# STM32BoardBeta2.net
KiCad netlist of a schematic drawn in EAGLE
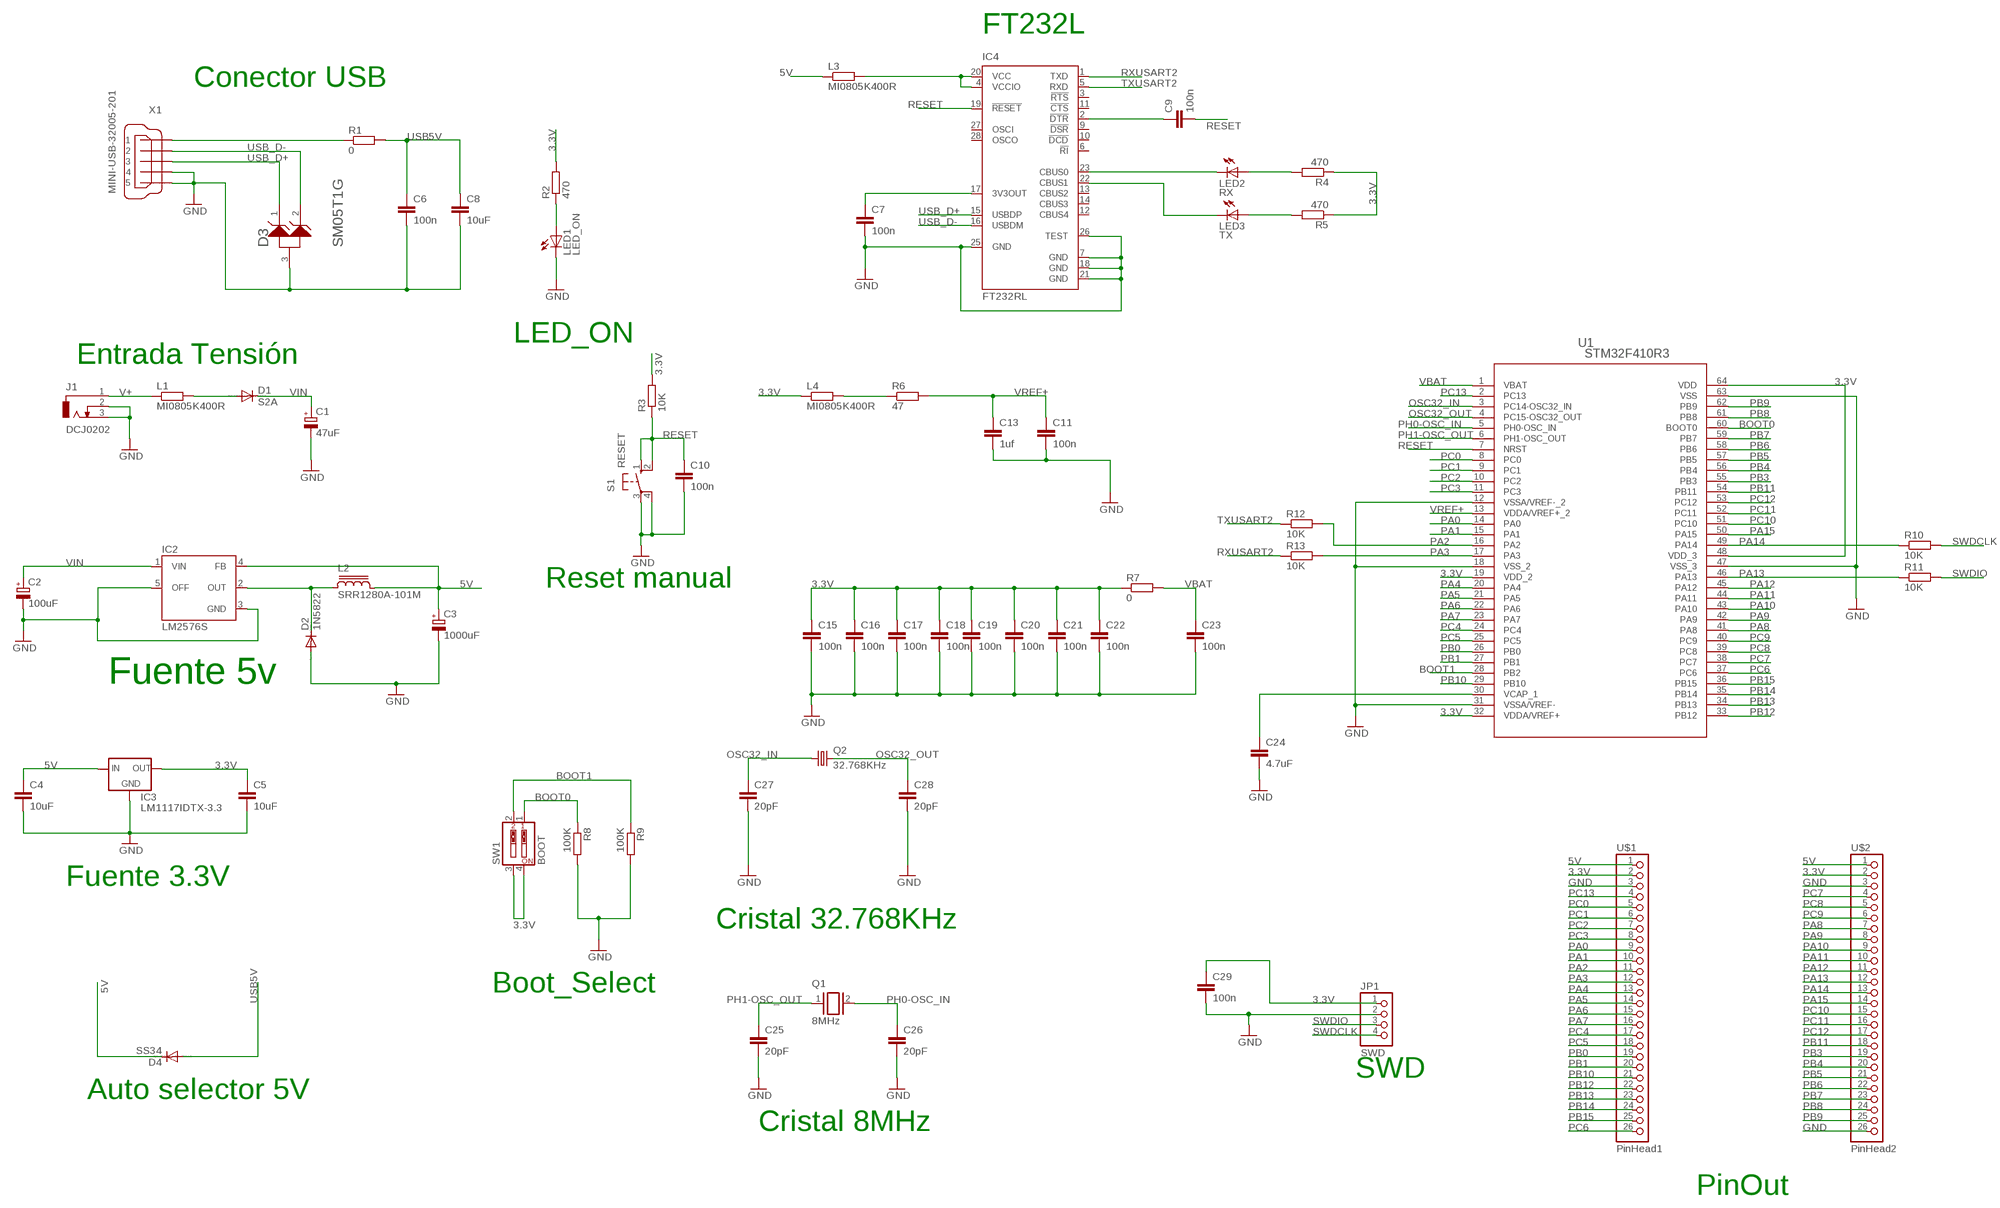
[diagram p0: schematic, sheet 1]

(export (version "E")
  (design (tool "Eeschema 10.0.6"))
  (components
    (comp (ref "C1")
      (value "47uF")
      (footprint "eagle-import:153CLV-0605")
      (libsource (lib "eagle-import") (part "CPOL-EU153CLV-0605"))
    )
    (comp (ref "C2")
      (value "100uF")
      (footprint "eagle-import:153CLV-0605")
      (libsource (lib "eagle-import") (part "CPOL-EU153CLV-0605"))
    )
    (comp (ref "C3")
      (value "1000uF")
      (footprint "eagle-import:E7,5-18")
      (libsource (lib "eagle-import") (part "CPOL-EUE7.5-18"))
    )
    (comp (ref "C4")
      (value "10uF")
      (footprint "eagle-import:C1206K")
      (libsource (lib "eagle-import") (part "C-EUC1206K"))
    )
    (comp (ref "C5")
      (value "10uF")
      (footprint "eagle-import:C1206K")
      (libsource (lib "eagle-import") (part "C-EUC1206K"))
    )
    (comp (ref "C6")
      (value "100n")
      (footprint "eagle-import:C0805K")
      (libsource (lib "eagle-import") (part "C-EUC0805K"))
    )
    (comp (ref "C7")
      (value "100n")
      (footprint "eagle-import:C0805K")
      (libsource (lib "eagle-import") (part "C-EUC0805K"))
    )
    (comp (ref "C8")
      (value "10uF")
      (footprint "eagle-import:C1206K")
      (libsource (lib "eagle-import") (part "C-EUC1206K"))
    )
    (comp (ref "C9")
      (value "100n")
      (footprint "eagle-import:C0805K")
      (libsource (lib "eagle-import") (part "C-EUC0805K"))
    )
    (comp (ref "C10")
      (value "100n")
      (footprint "eagle-import:C0805K")
      (libsource (lib "eagle-import") (part "C-EUC0805K"))
    )
    (comp (ref "C11")
      (value "100n")
      (footprint "eagle-import:C0201")
      (libsource (lib "eagle-import") (part "C-EUC0201"))
    )
    (comp (ref "C13")
      (value "1uf")
      (footprint "eagle-import:C0603")
      (libsource (lib "eagle-import") (part "C-EUC0603"))
    )
    (comp (ref "C15")
      (value "100n")
      (footprint "eagle-import:C0805K")
      (libsource (lib "eagle-import") (part "C-EUC0805K"))
    )
    (comp (ref "C16")
      (value "100n")
      (footprint "eagle-import:C0805K")
      (libsource (lib "eagle-import") (part "C-EUC0805K"))
    )
    (comp (ref "C17")
      (value "100n")
      (footprint "eagle-import:C0805K")
      (libsource (lib "eagle-import") (part "C-EUC0805K"))
    )
    (comp (ref "C18")
      (value "100n")
      (footprint "eagle-import:C0805K")
      (libsource (lib "eagle-import") (part "C-EUC0805K"))
    )
    (comp (ref "C19")
      (value "100n")
      (footprint "eagle-import:C0805K")
      (libsource (lib "eagle-import") (part "C-EUC0805K"))
    )
    (comp (ref "C20")
      (value "100n")
      (footprint "eagle-import:C0805K")
      (libsource (lib "eagle-import") (part "C-EUC0805K"))
    )
    (comp (ref "C21")
      (value "100n")
      (footprint "eagle-import:C0805K")
      (libsource (lib "eagle-import") (part "C-EUC0805K"))
    )
    (comp (ref "C22")
      (value "100n")
      (footprint "eagle-import:C0805K")
      (libsource (lib "eagle-import") (part "C-EUC0805K"))
    )
    (comp (ref "C23")
      (value "100n")
      (footprint "eagle-import:C0805K")
      (libsource (lib "eagle-import") (part "C-EUC0805K"))
    )
    (comp (ref "C24")
      (value "4.7uF")
      (footprint "eagle-import:C1206K")
      (libsource (lib "eagle-import") (part "C-EUC1206K"))
    )
    (comp (ref "C25")
      (value "20pF")
      (footprint "eagle-import:C0805K")
      (libsource (lib "eagle-import") (part "C-EUC0805K"))
    )
    (comp (ref "C26")
      (value "20pF")
      (footprint "eagle-import:C0805K")
      (libsource (lib "eagle-import") (part "C-EUC0805K"))
    )
    (comp (ref "C27")
      (value "20pF")
      (footprint "eagle-import:C0805K")
      (libsource (lib "eagle-import") (part "C-EUC0805K"))
    )
    (comp (ref "C28")
      (value "20pF")
      (footprint "eagle-import:C0805K")
      (libsource (lib "eagle-import") (part "C-EUC0805K"))
    )
    (comp (ref "C29")
      (value "100n")
      (footprint "eagle-import:C0201")
      (libsource (lib "eagle-import") (part "C-EUC0201"))
    )
    (comp (ref "D1")
      (value "S2A")
      (footprint "eagle-import:DO214AA")
      (libsource (lib "eagle-import") (part "DIODE-DO214AA"))
    )
    (comp (ref "D2")
      (value "1N5822")
      (footprint "eagle-import:DO41-10")
      (libsource (lib "eagle-import") (part "1N4004"))
    )
    (comp (ref "D3")
      (value "ON_SEMICONDUCTOR_SM05T1GON_SEMICONDUCTOR_SM05T1G_0_0")
      (footprint "eagle-import:ON_SEMICONDUCTOR_SM05T1G_0")
      (fields (field (name "MF") "On Semiconductor") (field (name "MPN") "SM05T1G"))
      (libsource (lib "eagle-import") (part "ON_SEMICONDUCTOR_SM05T1GON_SEMICONDUCTOR_SM05T1G_0_0"))
    )
    (comp (ref "D4")
      (value "SS34")
      (footprint "eagle-import:DO-214AC")
      (libsource (lib "eagle-import") (part "DIODE-DO-214AC"))
    )
    (comp (ref "IC2")
      (value "LM2576S")
      (footprint "eagle-import:TO263-5")
      (libsource (lib "eagle-import") (part "LM2576S"))
    )
    (comp (ref "IC3")
      (value "LM1117IDTX-3.3")
      (footprint "eagle-import:TO252")
      (libsource (lib "eagle-import") (part "LM1117IDTX-3.3"))
    )
    (comp (ref "IC4")
      (value "FT232RL")
      (footprint "eagle-import:SSOP28")
      (libsource (lib "eagle-import") (part "FT232RL"))
    )
    (comp (ref "J1")
      (value "DCJ0202")
      (footprint "eagle-import:DCJ0202")
      (libsource (lib "eagle-import") (part "DCJ0202"))
    )
    (comp (ref "JP1")
      (value "SWD")
      (footprint "eagle-import:1X04")
      (libsource (lib "eagle-import") (part "PINHD-1X4_2.54"))
    )
    (comp (ref "L1")
      (value "MI0805K400R")
      (footprint "eagle-import:M0805")
      (libsource (lib "eagle-import") (part "resistor_R-EU_M0805"))
    )
    (comp (ref "L2")
      (value "SRR1280A-101M")
      (footprint "eagle-import:SRR1280")
      (libsource (lib "eagle-import") (part "SRR1280"))
    )
    (comp (ref "L3")
      (value "MI0805K400R")
      (footprint "eagle-import:M0805")
      (libsource (lib "eagle-import") (part "resistor_R-EU_M0805"))
    )
    (comp (ref "L4")
      (value "MI0805K400R")
      (footprint "eagle-import:M0805")
      (libsource (lib "eagle-import") (part "resistor_R-EU_M0805"))
    )
    (comp (ref "LED1")
      (value "LED_ON")
      (footprint "eagle-import:CHIP-LED0805")
      (libsource (lib "eagle-import") (part "LEDCHIP-LED0805"))
    )
    (comp (ref "LED2")
      (value "RX")
      (footprint "eagle-import:CHIP-LED0805")
      (libsource (lib "eagle-import") (part "LEDCHIP-LED0805"))
    )
    (comp (ref "LED3")
      (value "TX")
      (footprint "eagle-import:CHIP-LED0805")
      (libsource (lib "eagle-import") (part "LEDCHIP-LED0805"))
    )
    (comp (ref "Q1")
      (value "8MHz")
      (footprint "eagle-import:QS")
      (libsource (lib "eagle-import") (part "XTAL/S"))
    )
    (comp (ref "Q2")
      (value "32.768KHz")
      (footprint "eagle-import:TC26V")
      (libsource (lib "eagle-import") (part "CRYSTALTC26V"))
    )
    (comp (ref "R1")
      (value "0")
      (footprint "eagle-import:M1206")
      (libsource (lib "eagle-import") (part "R-EU_M1206"))
    )
    (comp (ref "R2")
      (value "470")
      (footprint "eagle-import:R0805")
      (libsource (lib "eagle-import") (part "R-EU_R0805"))
    )
    (comp (ref "R3")
      (value "10K")
      (footprint "eagle-import:R1206")
      (libsource (lib "eagle-import") (part "R-EU_R1206"))
    )
    (comp (ref "R4")
      (value "470")
      (footprint "eagle-import:R0805")
      (libsource (lib "eagle-import") (part "R-EU_R0805"))
    )
    (comp (ref "R5")
      (value "470")
      (footprint "eagle-import:R0805")
      (libsource (lib "eagle-import") (part "R-EU_R0805"))
    )
    (comp (ref "R6")
      (value "47")
      (footprint "eagle-import:R0402")
      (libsource (lib "eagle-import") (part "R-EU_R0402"))
    )
    (comp (ref "R7")
      (value "0")
      (footprint "eagle-import:M1206")
      (libsource (lib "eagle-import") (part "R-EU_M1206"))
    )
    (comp (ref "R8")
      (value "100K")
      (footprint "eagle-import:R0805")
      (libsource (lib "eagle-import") (part "R-EU_R0805"))
    )
    (comp (ref "R9")
      (value "100K")
      (footprint "eagle-import:R0805")
      (libsource (lib "eagle-import") (part "R-EU_R0805"))
    )
    (comp (ref "R10")
      (value "10K")
      (footprint "eagle-import:R0805")
      (libsource (lib "eagle-import") (part "R-EU_R0805"))
    )
    (comp (ref "R11")
      (value "10K")
      (footprint "eagle-import:R0805")
      (libsource (lib "eagle-import") (part "R-EU_R0805"))
    )
    (comp (ref "R12")
      (value "10K")
      (footprint "eagle-import:R0805")
      (libsource (lib "eagle-import") (part "R-EU_R0805"))
    )
    (comp (ref "R13")
      (value "10K")
      (footprint "eagle-import:R0805")
      (libsource (lib "eagle-import") (part "R-EU_R0805"))
    )
    (comp (ref "S1")
      (value "RESET")
      (footprint "eagle-import:B3F-10XX")
      (fields (field (name "MPN") "B3F-1000"))
      (libsource (lib "eagle-import") (part "10-XX"))
    )
    (comp (ref "SW1")
      (value "BOOT")
      (footprint "eagle-import:EDG-02")
      (libsource (lib "eagle-import") (part "SW_DIP-2"))
    )
    (comp (ref "U$1")
      (value "PinHead1")
      (footprint "eagle-import:1X26")
      (libsource (lib "eagle-import") (part "PINHD-1X26_2.54"))
    )
    (comp (ref "U$2")
      (value "PinHead2")
      (footprint "eagle-import:1X26")
      (libsource (lib "eagle-import") (part "PINHD-1X26_2.54"))
    )
    (comp (ref "U1")
      (value "STM32F410R3")
      (footprint "eagle-import:LQFP64-10X10MM")
      (libsource (lib "eagle-import") (part "STM32F410R3"))
    )
    (comp (ref "X1")
      (value "MINI-USB-32005-201")
      (footprint "eagle-import:32005-201")
      (libsource (lib "eagle-import") (part "MINI-USB-32005-201"))
    )
  )
  (nets
    (net (code "1") (name "/3.3V") (class "Default")
      (node (ref "C15") (pin "1") (pinfunction "1_1") (pintype "passive"))
      (node (ref "C16") (pin "1") (pinfunction "1_1") (pintype "passive"))
      (node (ref "C17") (pin "1") (pinfunction "1_1") (pintype "passive"))
      (node (ref "C18") (pin "1") (pinfunction "1_1") (pintype "passive"))
      (node (ref "C19") (pin "1") (pinfunction "1_1") (pintype "passive"))
      (node (ref "C20") (pin "1") (pinfunction "1_1") (pintype "passive"))
      (node (ref "C21") (pin "1") (pinfunction "1_1") (pintype "passive"))
      (node (ref "C22") (pin "1") (pinfunction "1_1") (pintype "passive"))
      (node (ref "C29") (pin "1") (pinfunction "1_1") (pintype "passive"))
      (node (ref "C5") (pin "1") (pinfunction "1_1") (pintype "passive"))
      (node (ref "IC3") (pin "TAB") (pinfunction "OUT_TAB") (pintype "passive"))
      (node (ref "JP1") (pin "1") (pinfunction "1_1") (pintype "passive"))
      (node (ref "L4") (pin "1") (pinfunction "1_1") (pintype "passive"))
      (node (ref "R2") (pin "2") (pinfunction "2_2") (pintype "passive"))
      (node (ref "R3") (pin "2") (pinfunction "2_2") (pintype "passive"))
      (node (ref "R4") (pin "1") (pinfunction "1_1") (pintype "passive"))
      (node (ref "R5") (pin "1") (pinfunction "1_1") (pintype "passive"))
      (node (ref "R7") (pin "1") (pinfunction "1_1") (pintype "passive"))
      (node (ref "SW1") (pin "3") (pinfunction "3_3") (pintype "passive"))
      (node (ref "SW1") (pin "4") (pinfunction "4_4") (pintype "passive"))
      (node (ref "U$1") (pin "2") (pinfunction "2_2") (pintype "passive"))
      (node (ref "U$2") (pin "2") (pinfunction "2_2") (pintype "passive"))
      (node (ref "U1") (pin "19") (pinfunction "VDD_2_19") (pintype "power_in"))
      (node (ref "U1") (pin "32") (pinfunction "VDDA/VREF+_32") (pintype "power_in"))
      (node (ref "U1") (pin "48") (pinfunction "VDD_3_48") (pintype "power_in"))
      (node (ref "U1") (pin "64") (pinfunction "VDD_64") (pintype "power_in"))
    )
    (net (code "2") (name "/5V") (class "Default")
      (node (ref "C3") (pin "+") (pinfunction "+_+") (pintype "passive"))
      (node (ref "C4") (pin "1") (pinfunction "1_1") (pintype "passive"))
      (node (ref "D4") (pin "C") (pinfunction "C_C") (pintype "passive"))
      (node (ref "IC2") (pin "4") (pinfunction "FB_4") (pintype "input"))
      (node (ref "IC3") (pin "2") (pinfunction "IN_2") (pintype "input"))
      (node (ref "L2") (pin "2") (pinfunction "2_2") (pintype "passive"))
      (node (ref "L3") (pin "1") (pinfunction "1_1") (pintype "passive"))
      (node (ref "U$1") (pin "1") (pinfunction "1_1") (pintype "passive"))
      (node (ref "U$2") (pin "1") (pinfunction "1_1") (pintype "passive"))
    )
    (net (code "3") (name "/BOOT0") (class "Default")
      (node (ref "R8") (pin "1") (pinfunction "1_1") (pintype "passive"))
      (node (ref "SW1") (pin "1") (pinfunction "1_1") (pintype "passive"))
      (node (ref "U1") (pin "60") (pinfunction "BOOT0_60") (pintype "input"))
    )
    (net (code "4") (name "/BOOT1") (class "Default")
      (node (ref "R9") (pin "1") (pinfunction "1_1") (pintype "passive"))
      (node (ref "SW1") (pin "2") (pinfunction "2_2") (pintype "passive"))
      (node (ref "U1") (pin "28") (pinfunction "PB2_28") (pintype "passive"))
    )
    (net (code "5") (name "/OSC32_IN") (class "Default")
      (node (ref "C27") (pin "1") (pinfunction "1_1") (pintype "passive"))
      (node (ref "Q2") (pin "1") (pinfunction "1_1") (pintype "passive"))
      (node (ref "U1") (pin "3") (pinfunction "PC14-OSC32_IN_3") (pintype "passive"))
    )
    (net (code "6") (name "/OSC32_OUT") (class "Default")
      (node (ref "C28") (pin "1") (pinfunction "1_1") (pintype "passive"))
      (node (ref "Q2") (pin "2") (pinfunction "2_2") (pintype "passive"))
      (node (ref "U1") (pin "4") (pinfunction "PC15-OSC32_OUT_4") (pintype "passive"))
    )
    (net (code "7") (name "/PA0") (class "Default")
      (node (ref "U$1") (pin "9") (pinfunction "9_9") (pintype "passive"))
      (node (ref "U1") (pin "14") (pinfunction "PA0_14") (pintype "passive"))
    )
    (net (code "8") (name "/PA1") (class "Default")
      (node (ref "U$1") (pin "10") (pinfunction "10_10") (pintype "passive"))
      (node (ref "U1") (pin "15") (pinfunction "PA1_15") (pintype "passive"))
    )
    (net (code "9") (name "/PA2") (class "Default")
      (node (ref "R12") (pin "2") (pinfunction "2_2") (pintype "passive"))
      (node (ref "U$1") (pin "11") (pinfunction "11_11") (pintype "passive"))
      (node (ref "U1") (pin "16") (pinfunction "PA2_16") (pintype "passive"))
    )
    (net (code "10") (name "/PA3") (class "Default")
      (node (ref "R13") (pin "2") (pinfunction "2_2") (pintype "passive"))
      (node (ref "U$1") (pin "12") (pinfunction "12_12") (pintype "passive"))
      (node (ref "U1") (pin "17") (pinfunction "PA3_17") (pintype "passive"))
    )
    (net (code "11") (name "/PA4") (class "Default")
      (node (ref "U$1") (pin "13") (pinfunction "13_13") (pintype "passive"))
      (node (ref "U1") (pin "20") (pinfunction "PA4_20") (pintype "passive"))
    )
    (net (code "12") (name "/PA5") (class "Default")
      (node (ref "U$1") (pin "14") (pinfunction "14_14") (pintype "passive"))
      (node (ref "U1") (pin "21") (pinfunction "PA5_21") (pintype "passive"))
    )
    (net (code "13") (name "/PA6") (class "Default")
      (node (ref "U$1") (pin "15") (pinfunction "15_15") (pintype "passive"))
      (node (ref "U1") (pin "22") (pinfunction "PA6_22") (pintype "passive"))
    )
    (net (code "14") (name "/PA7") (class "Default")
      (node (ref "U$1") (pin "16") (pinfunction "16_16") (pintype "passive"))
      (node (ref "U1") (pin "23") (pinfunction "PA7_23") (pintype "passive"))
    )
    (net (code "15") (name "/PA8") (class "Default")
      (node (ref "U$2") (pin "7") (pinfunction "7_7") (pintype "passive"))
      (node (ref "U1") (pin "41") (pinfunction "PA8_41") (pintype "passive"))
    )
    (net (code "16") (name "/PA9") (class "Default")
      (node (ref "U$2") (pin "8") (pinfunction "8_8") (pintype "passive"))
      (node (ref "U1") (pin "42") (pinfunction "PA9_42") (pintype "passive"))
    )
    (net (code "17") (name "/PA10") (class "Default")
      (node (ref "U$2") (pin "9") (pinfunction "9_9") (pintype "passive"))
      (node (ref "U1") (pin "43") (pinfunction "PA10_43") (pintype "passive"))
    )
    (net (code "18") (name "/PA11") (class "Default")
      (node (ref "U$2") (pin "10") (pinfunction "10_10") (pintype "passive"))
      (node (ref "U1") (pin "44") (pinfunction "PA11_44") (pintype "passive"))
    )
    (net (code "19") (name "/PA12") (class "Default")
      (node (ref "U$2") (pin "11") (pinfunction "11_11") (pintype "passive"))
      (node (ref "U1") (pin "45") (pinfunction "PA12_45") (pintype "passive"))
    )
    (net (code "20") (name "/PA13") (class "Default")
      (node (ref "R11") (pin "1") (pinfunction "1_1") (pintype "passive"))
      (node (ref "U$2") (pin "12") (pinfunction "12_12") (pintype "passive"))
      (node (ref "U1") (pin "46") (pinfunction "PA13_46") (pintype "passive"))
    )
    (net (code "21") (name "/PA14") (class "Default")
      (node (ref "R10") (pin "1") (pinfunction "1_1") (pintype "passive"))
      (node (ref "U$2") (pin "13") (pinfunction "13_13") (pintype "passive"))
      (node (ref "U1") (pin "49") (pinfunction "PA14_49") (pintype "passive"))
    )
    (net (code "22") (name "/PA15") (class "Default")
      (node (ref "U$2") (pin "14") (pinfunction "14_14") (pintype "passive"))
      (node (ref "U1") (pin "50") (pinfunction "PA15_50") (pintype "passive"))
    )
    (net (code "23") (name "/PB0") (class "Default")
      (node (ref "U$1") (pin "19") (pinfunction "19_19") (pintype "passive"))
      (node (ref "U1") (pin "26") (pinfunction "PB0_26") (pintype "passive"))
    )
    (net (code "24") (name "/PB1") (class "Default")
      (node (ref "U$1") (pin "20") (pinfunction "20_20") (pintype "passive"))
      (node (ref "U1") (pin "27") (pinfunction "PB1_27") (pintype "passive"))
    )
    (net (code "25") (name "/PB3") (class "Default")
      (node (ref "U$2") (pin "19") (pinfunction "19_19") (pintype "passive"))
      (node (ref "U1") (pin "55") (pinfunction "PB3_55") (pintype "passive"))
    )
    (net (code "26") (name "/PB4") (class "Default")
      (node (ref "U$2") (pin "20") (pinfunction "20_20") (pintype "passive"))
      (node (ref "U1") (pin "56") (pinfunction "PB4_56") (pintype "passive"))
    )
    (net (code "27") (name "/PB5") (class "Default")
      (node (ref "U$2") (pin "21") (pinfunction "21_21") (pintype "passive"))
      (node (ref "U1") (pin "57") (pinfunction "PB5_57") (pintype "passive"))
    )
    (net (code "28") (name "/PB6") (class "Default")
      (node (ref "U$2") (pin "22") (pinfunction "22_22") (pintype "passive"))
      (node (ref "U1") (pin "58") (pinfunction "PB6_58") (pintype "passive"))
    )
    (net (code "29") (name "/PB7") (class "Default")
      (node (ref "U$2") (pin "23") (pinfunction "23_23") (pintype "passive"))
      (node (ref "U1") (pin "59") (pinfunction "PB7_59") (pintype "passive"))
    )
    (net (code "30") (name "/PB8") (class "Default")
      (node (ref "U$2") (pin "24") (pinfunction "24_24") (pintype "passive"))
      (node (ref "U1") (pin "61") (pinfunction "PB8_61") (pintype "passive"))
    )
    (net (code "31") (name "/PB9") (class "Default")
      (node (ref "U$2") (pin "25") (pinfunction "25_25") (pintype "passive"))
      (node (ref "U1") (pin "62") (pinfunction "PB9_62") (pintype "passive"))
    )
    (net (code "32") (name "/PB10") (class "Default")
      (node (ref "U$1") (pin "21") (pinfunction "21_21") (pintype "passive"))
      (node (ref "U1") (pin "29") (pinfunction "PB10_29") (pintype "passive"))
    )
    (net (code "33") (name "/PB11") (class "Default")
      (node (ref "U$2") (pin "18") (pinfunction "18_18") (pintype "passive"))
      (node (ref "U1") (pin "54") (pinfunction "PB11_54") (pintype "passive"))
    )
    (net (code "34") (name "/PB12") (class "Default")
      (node (ref "U$1") (pin "22") (pinfunction "22_22") (pintype "passive"))
      (node (ref "U1") (pin "33") (pinfunction "PB12_33") (pintype "passive"))
    )
    (net (code "35") (name "/PB13") (class "Default")
      (node (ref "U$1") (pin "23") (pinfunction "23_23") (pintype "passive"))
      (node (ref "U1") (pin "34") (pinfunction "PB13_34") (pintype "passive"))
    )
    (net (code "36") (name "/PB14") (class "Default")
      (node (ref "U$1") (pin "24") (pinfunction "24_24") (pintype "passive"))
      (node (ref "U1") (pin "35") (pinfunction "PB14_35") (pintype "passive"))
    )
    (net (code "37") (name "/PB15") (class "Default")
      (node (ref "U$1") (pin "25") (pinfunction "25_25") (pintype "passive"))
      (node (ref "U1") (pin "36") (pinfunction "PB15_36") (pintype "passive"))
    )
    (net (code "38") (name "/PC0") (class "Default")
      (node (ref "U$1") (pin "5") (pinfunction "5_5") (pintype "passive"))
      (node (ref "U1") (pin "8") (pinfunction "PC0_8") (pintype "passive"))
    )
    (net (code "39") (name "/PC1") (class "Default")
      (node (ref "U$1") (pin "6") (pinfunction "6_6") (pintype "passive"))
      (node (ref "U1") (pin "9") (pinfunction "PC1_9") (pintype "passive"))
    )
    (net (code "40") (name "/PC2") (class "Default")
      (node (ref "U$1") (pin "7") (pinfunction "7_7") (pintype "passive"))
      (node (ref "U1") (pin "10") (pinfunction "PC2_10") (pintype "passive"))
    )
    (net (code "41") (name "/PC3") (class "Default")
      (node (ref "U$1") (pin "8") (pinfunction "8_8") (pintype "passive"))
      (node (ref "U1") (pin "11") (pinfunction "PC3_11") (pintype "passive"))
    )
    (net (code "42") (name "/PC4") (class "Default")
      (node (ref "U$1") (pin "17") (pinfunction "17_17") (pintype "passive"))
      (node (ref "U1") (pin "24") (pinfunction "PC4_24") (pintype "passive"))
    )
    (net (code "43") (name "/PC5") (class "Default")
      (node (ref "U$1") (pin "18") (pinfunction "18_18") (pintype "passive"))
      (node (ref "U1") (pin "25") (pinfunction "PC5_25") (pintype "passive"))
    )
    (net (code "44") (name "/PC6") (class "Default")
      (node (ref "U$1") (pin "26") (pinfunction "26_26") (pintype "passive"))
      (node (ref "U1") (pin "37") (pinfunction "PC6_37") (pintype "passive"))
    )
    (net (code "45") (name "/PC7") (class "Default")
      (node (ref "U$2") (pin "4") (pinfunction "4_4") (pintype "passive"))
      (node (ref "U1") (pin "38") (pinfunction "PC7_38") (pintype "passive"))
    )
    (net (code "46") (name "/PC8") (class "Default")
      (node (ref "U$2") (pin "5") (pinfunction "5_5") (pintype "passive"))
      (node (ref "U1") (pin "39") (pinfunction "PC8_39") (pintype "passive"))
    )
    (net (code "47") (name "/PC9") (class "Default")
      (node (ref "U$2") (pin "6") (pinfunction "6_6") (pintype "passive"))
      (node (ref "U1") (pin "40") (pinfunction "PC9_40") (pintype "passive"))
    )
    (net (code "48") (name "/PC10") (class "Default")
      (node (ref "U$2") (pin "15") (pinfunction "15_15") (pintype "passive"))
      (node (ref "U1") (pin "51") (pinfunction "PC10_51") (pintype "passive"))
    )
    (net (code "49") (name "/PC11") (class "Default")
      (node (ref "U$2") (pin "16") (pinfunction "16_16") (pintype "passive"))
      (node (ref "U1") (pin "52") (pinfunction "PC11_52") (pintype "passive"))
    )
    (net (code "50") (name "/PC12") (class "Default")
      (node (ref "U$2") (pin "17") (pinfunction "17_17") (pintype "passive"))
      (node (ref "U1") (pin "53") (pinfunction "PC12_53") (pintype "passive"))
    )
    (net (code "51") (name "/PC13") (class "Default")
      (node (ref "U$1") (pin "4") (pinfunction "4_4") (pintype "passive"))
      (node (ref "U1") (pin "2") (pinfunction "PC13_2") (pintype "passive"))
    )
    (net (code "52") (name "/PH0-OSC_IN") (class "Default")
      (node (ref "C26") (pin "1") (pinfunction "1_1") (pintype "passive"))
      (node (ref "Q1") (pin "2") (pinfunction "2_2") (pintype "passive"))
      (node (ref "U1") (pin "5") (pinfunction "PH0-OSC_IN_5") (pintype "passive"))
    )
    (net (code "53") (name "/PH1-OSC_OUT") (class "Default")
      (node (ref "C25") (pin "1") (pinfunction "1_1") (pintype "passive"))
      (node (ref "Q1") (pin "1") (pinfunction "1_1") (pintype "passive"))
      (node (ref "U1") (pin "6") (pinfunction "PH1-OSC_OUT_6") (pintype "passive"))
    )
    (net (code "54") (name "/RESET") (class "Default")
      (node (ref "C10") (pin "1") (pinfunction "1_1") (pintype "passive"))
      (node (ref "C9") (pin "2") (pinfunction "2_2") (pintype "passive"))
      (node (ref "IC4") (pin "19") (pinfunction "~{RESET}_19") (pintype "input"))
      (node (ref "R3") (pin "1") (pinfunction "1_1") (pintype "passive"))
      (node (ref "S1") (pin "1") (pinfunction "S_1") (pintype "passive"))
      (node (ref "S1") (pin "2") (pinfunction "S1_2") (pintype "passive"))
      (node (ref "U1") (pin "7") (pinfunction "NRST_7") (pintype "passive"))
    )
    (net (code "55") (name "/RXUSART2") (class "Default")
      (node (ref "IC4") (pin "1") (pinfunction "TXD_1") (pintype "output"))
      (node (ref "R13") (pin "1") (pinfunction "1_1") (pintype "passive"))
    )
    (net (code "56") (name "/SWDCLK") (class "Default")
      (node (ref "JP1") (pin "4") (pinfunction "4_4") (pintype "passive"))
      (node (ref "R10") (pin "2") (pinfunction "2_2") (pintype "passive"))
    )
    (net (code "57") (name "/SWDIO") (class "Default")
      (node (ref "JP1") (pin "3") (pinfunction "3_3") (pintype "passive"))
      (node (ref "R11") (pin "2") (pinfunction "2_2") (pintype "passive"))
    )
    (net (code "58") (name "/TXUSART2") (class "Default")
      (node (ref "IC4") (pin "5") (pinfunction "RXD_5") (pintype "input"))
      (node (ref "R12") (pin "1") (pinfunction "1_1") (pintype "passive"))
    )
    (net (code "59") (name "/USB5V") (class "Default")
      (node (ref "C6") (pin "1") (pinfunction "1_1") (pintype "passive"))
      (node (ref "C8") (pin "1") (pinfunction "1_1") (pintype "passive"))
      (node (ref "D4") (pin "A") (pinfunction "A_A") (pintype "passive"))
      (node (ref "R1") (pin "2") (pinfunction "2_2") (pintype "passive"))
    )
    (net (code "60") (name "/USB_D+") (class "Default")
      (node (ref "D3") (pin "1") (pinfunction "K1_1") (pintype "bidirectional"))
      (node (ref "IC4") (pin "15") (pinfunction "USBDP_15") (pintype "bidirectional"))
      (node (ref "X1") (pin "3") (pinfunction "3_3") (pintype "passive"))
    )
    (net (code "61") (name "/USB_D-") (class "Default")
      (node (ref "D3") (pin "2") (pinfunction "K2_2") (pintype "bidirectional"))
      (node (ref "IC4") (pin "16") (pinfunction "USBDM_16") (pintype "bidirectional"))
      (node (ref "X1") (pin "2") (pinfunction "2_2") (pintype "passive"))
    )
    (net (code "62") (name "/V+") (class "Default")
      (node (ref "J1") (pin "1") (pinfunction "1_1") (pintype "passive"))
      (node (ref "L1") (pin "1") (pinfunction "1_1") (pintype "passive"))
    )
    (net (code "63") (name "/VBAT") (class "Default")
      (node (ref "C23") (pin "1") (pinfunction "1_1") (pintype "passive"))
      (node (ref "R7") (pin "2") (pinfunction "2_2") (pintype "passive"))
      (node (ref "U1") (pin "1") (pinfunction "VBAT_1") (pintype "power_in"))
    )
    (net (code "64") (name "/VIN") (class "Default")
      (node (ref "C1") (pin "+") (pinfunction "+_+") (pintype "passive"))
      (node (ref "C2") (pin "+") (pinfunction "+_+") (pintype "passive"))
      (node (ref "D1") (pin "C") (pinfunction "C_C") (pintype "passive"))
      (node (ref "IC2") (pin "1") (pinfunction "VIN_1") (pintype "power_in"))
    )
    (net (code "65") (name "/VREF+") (class "Default")
      (node (ref "C11") (pin "1") (pinfunction "1_1") (pintype "passive"))
      (node (ref "C13") (pin "1") (pinfunction "1_1") (pintype "passive"))
      (node (ref "R6") (pin "2") (pinfunction "2_2") (pintype "passive"))
      (node (ref "U1") (pin "13") (pinfunction "VDDA/VREF+_2_13") (pintype "power_in"))
    )
    (net (code "66") (name "GND") (class "Default")
      (node (ref "C1") (pin "-") (pinfunction "-_-") (pintype "passive"))
      (node (ref "C10") (pin "2") (pinfunction "2_2") (pintype "passive"))
      (node (ref "C11") (pin "2") (pinfunction "2_2") (pintype "passive"))
      (node (ref "C13") (pin "2") (pinfunction "2_2") (pintype "passive"))
      (node (ref "C15") (pin "2") (pinfunction "2_2") (pintype "passive"))
      (node (ref "C16") (pin "2") (pinfunction "2_2") (pintype "passive"))
      (node (ref "C17") (pin "2") (pinfunction "2_2") (pintype "passive"))
      (node (ref "C18") (pin "2") (pinfunction "2_2") (pintype "passive"))
      (node (ref "C19") (pin "2") (pinfunction "2_2") (pintype "passive"))
      (node (ref "C2") (pin "-") (pinfunction "-_-") (pintype "passive"))
      (node (ref "C20") (pin "2") (pinfunction "2_2") (pintype "passive"))
      (node (ref "C21") (pin "2") (pinfunction "2_2") (pintype "passive"))
      (node (ref "C22") (pin "2") (pinfunction "2_2") (pintype "passive"))
      (node (ref "C23") (pin "2") (pinfunction "2_2") (pintype "passive"))
      (node (ref "C24") (pin "2") (pinfunction "2_2") (pintype "passive"))
      (node (ref "C25") (pin "2") (pinfunction "2_2") (pintype "passive"))
      (node (ref "C26") (pin "2") (pinfunction "2_2") (pintype "passive"))
      (node (ref "C27") (pin "2") (pinfunction "2_2") (pintype "passive"))
      (node (ref "C28") (pin "2") (pinfunction "2_2") (pintype "passive"))
      (node (ref "C29") (pin "2") (pinfunction "2_2") (pintype "passive"))
      (node (ref "C3") (pin "-") (pinfunction "-_-") (pintype "passive"))
      (node (ref "C4") (pin "2") (pinfunction "2_2") (pintype "passive"))
      (node (ref "C5") (pin "2") (pinfunction "2_2") (pintype "passive"))
      (node (ref "C6") (pin "2") (pinfunction "2_2") (pintype "passive"))
      (node (ref "C7") (pin "2") (pinfunction "2_2") (pintype "passive"))
      (node (ref "C8") (pin "2") (pinfunction "2_2") (pintype "passive"))
      (node (ref "D2") (pin "A") (pinfunction "A_A") (pintype "passive"))
      (node (ref "D3") (pin "3") (pinfunction "A_3") (pintype "bidirectional"))
      (node (ref "IC2") (pin "3") (pinfunction "GND_3") (pintype "power_in"))
      (node (ref "IC2") (pin "5") (pinfunction "OFF_5") (pintype "input"))
      (node (ref "IC3") (pin "1") (pinfunction "GND_1") (pintype "input"))
      (node (ref "IC4") (pin "18") (pinfunction "GND_18") (pintype "power_in"))
      (node (ref "IC4") (pin "21") (pinfunction "GND_21") (pintype "power_in"))
      (node (ref "IC4") (pin "25") (pinfunction "GND_25") (pintype "power_in"))
      (node (ref "IC4") (pin "26") (pinfunction "TEST_26") (pintype "input"))
      (node (ref "IC4") (pin "7") (pinfunction "GND_7") (pintype "power_in"))
      (node (ref "J1") (pin "2") (pinfunction "2_2") (pintype "passive"))
      (node (ref "J1") (pin "3") (pinfunction "3_3") (pintype "passive"))
      (node (ref "JP1") (pin "2") (pinfunction "2_2") (pintype "passive"))
      (node (ref "LED1") (pin "C") (pinfunction "C_C") (pintype "passive"))
      (node (ref "R8") (pin "2") (pinfunction "2_2") (pintype "passive"))
      (node (ref "R9") (pin "2") (pinfunction "2_2") (pintype "passive"))
      (node (ref "S1") (pin "3") (pinfunction "P_3") (pintype "passive"))
      (node (ref "S1") (pin "4") (pinfunction "P1_4") (pintype "passive"))
      (node (ref "U$1") (pin "3") (pinfunction "3_3") (pintype "passive"))
      (node (ref "U$2") (pin "26") (pinfunction "26_26") (pintype "passive"))
      (node (ref "U$2") (pin "3") (pinfunction "3_3") (pintype "passive"))
      (node (ref "U1") (pin "12") (pinfunction "VSSA/VREF-_2_12") (pintype "power_in"))
      (node (ref "U1") (pin "18") (pinfunction "VSS_2_18") (pintype "power_in"))
      (node (ref "U1") (pin "31") (pinfunction "VSSA/VREF-_31") (pintype "power_in"))
      (node (ref "U1") (pin "47") (pinfunction "VSS_3_47") (pintype "power_in"))
      (node (ref "U1") (pin "63") (pinfunction "VSS_63") (pintype "power_in"))
      (node (ref "X1") (pin "4") (pinfunction "4_4") (pintype "passive"))
      (node (ref "X1") (pin "5") (pinfunction "5_5") (pintype "passive"))
    )
    (net (code "67") (name "Net-(D1-PadA)") (class "Default")
      (node (ref "D1") (pin "A") (pinfunction "A_A") (pintype "passive"))
      (node (ref "L1") (pin "2") (pinfunction "2_2") (pintype "passive"))
    )
    (net (code "68") (name "Net-(IC2-OUT)") (class "Default")
      (node (ref "D2") (pin "C") (pinfunction "C_C") (pintype "passive"))
      (node (ref "IC2") (pin "2") (pinfunction "OUT_2") (pintype "output"))
      (node (ref "L2") (pin "1") (pinfunction "1_1") (pintype "passive"))
    )
    (net (code "69") (name "Net-(IC4-3V3OUT)") (class "Default")
      (node (ref "C7") (pin "1") (pinfunction "1_1") (pintype "passive"))
      (node (ref "IC4") (pin "17") (pinfunction "3V3OUT_17") (pintype "output"))
    )
    (net (code "70") (name "Net-(IC4-CBUS0)") (class "Default")
      (node (ref "IC4") (pin "23") (pinfunction "CBUS0_23") (pintype "bidirectional"))
      (node (ref "LED2") (pin "C") (pinfunction "C_C") (pintype "passive"))
    )
    (net (code "71") (name "Net-(IC4-CBUS1)") (class "Default")
      (node (ref "IC4") (pin "22") (pinfunction "CBUS1_22") (pintype "bidirectional"))
      (node (ref "LED3") (pin "C") (pinfunction "C_C") (pintype "passive"))
    )
    (net (code "72") (name "Net-(IC4-VCC)") (class "Default")
      (node (ref "IC4") (pin "20") (pinfunction "VCC_20") (pintype "power_in"))
      (node (ref "IC4") (pin "4") (pinfunction "VCCIO_4") (pintype "power_in"))
      (node (ref "L3") (pin "2") (pinfunction "2_2") (pintype "passive"))
    )
    (net (code "73") (name "Net-(IC4-~{DTR})") (class "Default")
      (node (ref "C9") (pin "1") (pinfunction "1_1") (pintype "passive"))
      (node (ref "IC4") (pin "2") (pinfunction "~{DTR}_2") (pintype "output"))
    )
    (net (code "74") (name "Net-(L4-Pad2)") (class "Default")
      (node (ref "L4") (pin "2") (pinfunction "2_2") (pintype "passive"))
      (node (ref "R6") (pin "1") (pinfunction "1_1") (pintype "passive"))
    )
    (net (code "75") (name "Net-(LED1-PadA)") (class "Default")
      (node (ref "LED1") (pin "A") (pinfunction "A_A") (pintype "passive"))
      (node (ref "R2") (pin "1") (pinfunction "1_1") (pintype "passive"))
    )
    (net (code "76") (name "Net-(LED2-PadA)") (class "Default")
      (node (ref "LED2") (pin "A") (pinfunction "A_A") (pintype "passive"))
      (node (ref "R4") (pin "2") (pinfunction "2_2") (pintype "passive"))
    )
    (net (code "77") (name "Net-(LED3-PadA)") (class "Default")
      (node (ref "LED3") (pin "A") (pinfunction "A_A") (pintype "passive"))
      (node (ref "R5") (pin "2") (pinfunction "2_2") (pintype "passive"))
    )
    (net (code "78") (name "Net-(R1-Pad1)") (class "Default")
      (node (ref "R1") (pin "1") (pinfunction "1_1") (pintype "passive"))
      (node (ref "X1") (pin "1") (pinfunction "1_1") (pintype "passive"))
    )
    (net (code "79") (name "Net-(U1-VCAP_1)") (class "Default")
      (node (ref "C24") (pin "1") (pinfunction "1_1") (pintype "passive"))
      (node (ref "U1") (pin "30") (pinfunction "VCAP_1_30") (pintype "power_in"))
    )
    (net (code "80") (name "unconnected-(IC4-CBUS2-Pad13)") (class "Default")
      (node (ref "IC4") (pin "13") (pinfunction "CBUS2_13") (pintype "bidirectional"))
    )
    (net (code "81") (name "unconnected-(IC4-CBUS3-Pad14)") (class "Default")
      (node (ref "IC4") (pin "14") (pinfunction "CBUS3_14") (pintype "bidirectional"))
    )
    (net (code "82") (name "unconnected-(IC4-CBUS4-Pad12)") (class "Default")
      (node (ref "IC4") (pin "12") (pinfunction "CBUS4_12") (pintype "bidirectional"))
    )
    (net (code "83") (name "unconnected-(IC4-OSCI-Pad27)") (class "Default")
      (node (ref "IC4") (pin "27") (pinfunction "OSCI_27") (pintype "input"))
    )
    (net (code "84") (name "unconnected-(IC4-OSCO-Pad28)") (class "Default")
      (node (ref "IC4") (pin "28") (pinfunction "OSCO_28") (pintype "output"))
    )
    (net (code "85") (name "unconnected-(IC4-~{CTS}-Pad11)") (class "Default")
      (node (ref "IC4") (pin "11") (pinfunction "~{CTS}_11") (pintype "input"))
    )
    (net (code "86") (name "unconnected-(IC4-~{DCD}-Pad10)") (class "Default")
      (node (ref "IC4") (pin "10") (pinfunction "~{DCD}_10") (pintype "input"))
    )
    (net (code "87") (name "unconnected-(IC4-~{DSR}-Pad9)") (class "Default")
      (node (ref "IC4") (pin "9") (pinfunction "~{DSR}_9") (pintype "input"))
    )
    (net (code "88") (name "unconnected-(IC4-~{RI}-Pad6)") (class "Default")
      (node (ref "IC4") (pin "6") (pinfunction "~{RI}_6") (pintype "input"))
    )
    (net (code "89") (name "unconnected-(IC4-~{RTS}-Pad3)") (class "Default")
      (node (ref "IC4") (pin "3") (pinfunction "~{RTS}_3") (pintype "output"))
    )
  )
)
